# buttons.net
KiCad netlist of a schematic drawn in Altium Designer
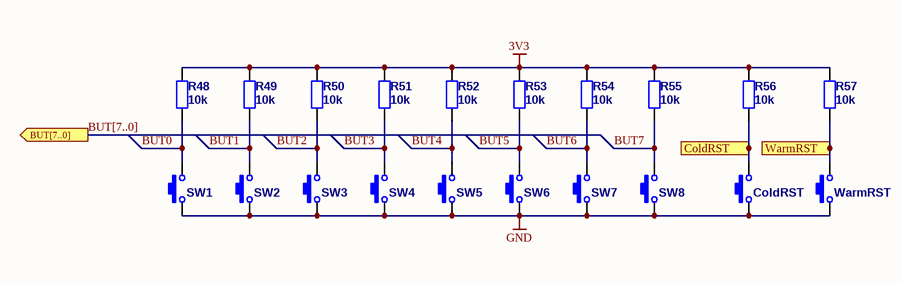
[diagram p0: buttons.SchDoc]

(export (version "E")
  (design (tool "Eeschema 10.0.6"))
  (components
    (comp (ref "ColdRST")
      (value "TACTM-67N-F")
      (footprint "DTSM-6")
      (description "6x6mm SMD Tactile SPST-NO Switch")
      (libsource (lib "microswitches") (part "TACTM-67N-F"))
    )
    (comp (ref "R48")
      (value "10k")
      (footprint "R0603")
      (description "Resistor")
      (libsource (lib "resistors") (part "Res"))
    )
    (comp (ref "R49")
      (value "10k")
      (footprint "R0603")
      (description "Resistor")
      (libsource (lib "resistors") (part "Res"))
    )
    (comp (ref "R50")
      (value "10k")
      (footprint "R0603")
      (description "Resistor")
      (libsource (lib "resistors") (part "Res"))
    )
    (comp (ref "R51")
      (value "10k")
      (footprint "R0603")
      (description "Resistor")
      (libsource (lib "resistors") (part "Res"))
    )
    (comp (ref "R52")
      (value "10k")
      (footprint "R0603")
      (description "Resistor")
      (libsource (lib "resistors") (part "Res"))
    )
    (comp (ref "R53")
      (value "10k")
      (footprint "R0603")
      (description "Resistor")
      (libsource (lib "resistors") (part "Res"))
    )
    (comp (ref "R54")
      (value "10k")
      (footprint "R0603")
      (description "Resistor")
      (libsource (lib "resistors") (part "Res"))
    )
    (comp (ref "R55")
      (value "10k")
      (footprint "R0603")
      (description "Resistor")
      (libsource (lib "resistors") (part "Res"))
    )
    (comp (ref "R56")
      (value "10k")
      (footprint "R0603")
      (description "Resistor")
      (libsource (lib "resistors") (part "Res"))
    )
    (comp (ref "R57")
      (value "10k")
      (footprint "R0603")
      (description "Resistor")
      (libsource (lib "resistors") (part "Res"))
    )
    (comp (ref "SW1")
      (value "TACTM-67N-F")
      (footprint "DTSM-6")
      (description "6x6mm SMD Tactile SPST-NO Switch")
      (libsource (lib "microswitches") (part "TACTM-67N-F"))
    )
    (comp (ref "SW2")
      (value "TACTM-67N-F")
      (footprint "DTSM-6")
      (description "6x6mm SMD Tactile SPST-NO Switch")
      (libsource (lib "microswitches") (part "TACTM-67N-F"))
    )
    (comp (ref "SW3")
      (value "TACTM-67N-F")
      (footprint "DTSM-6")
      (description "6x6mm SMD Tactile SPST-NO Switch")
      (libsource (lib "microswitches") (part "TACTM-67N-F"))
    )
    (comp (ref "SW4")
      (value "TACTM-67N-F")
      (footprint "DTSM-6")
      (description "6x6mm SMD Tactile SPST-NO Switch")
      (libsource (lib "microswitches") (part "TACTM-67N-F"))
    )
    (comp (ref "SW5")
      (value "TACTM-67N-F")
      (footprint "DTSM-6")
      (description "6x6mm SMD Tactile SPST-NO Switch")
      (libsource (lib "microswitches") (part "TACTM-67N-F"))
    )
    (comp (ref "SW6")
      (value "TACTM-67N-F")
      (footprint "DTSM-6")
      (description "6x6mm SMD Tactile SPST-NO Switch")
      (libsource (lib "microswitches") (part "TACTM-67N-F"))
    )
    (comp (ref "SW7")
      (value "TACTM-67N-F")
      (footprint "DTSM-6")
      (description "6x6mm SMD Tactile SPST-NO Switch")
      (libsource (lib "microswitches") (part "TACTM-67N-F"))
    )
    (comp (ref "SW8")
      (value "TACTM-67N-F")
      (footprint "DTSM-6")
      (description "6x6mm SMD Tactile SPST-NO Switch")
      (libsource (lib "microswitches") (part "TACTM-67N-F"))
    )
    (comp (ref "WarmRST")
      (value "TACTM-67N-F")
      (footprint "DTSM-6")
      (description "6x6mm SMD Tactile SPST-NO Switch")
      (libsource (lib "microswitches") (part "TACTM-67N-F"))
    )
  )
  (nets
    (net (code "1") (name "/BUT0") (class "Default")
      (node (ref "R48") (pin "1") (pinfunction "1_1") (pintype "passive"))
      (node (ref "SW1") (pin "2") (pinfunction "2_2") (pintype "passive"))
    )
    (net (code "2") (name "/BUT1") (class "Default")
      (node (ref "R49") (pin "1") (pinfunction "1_1") (pintype "passive"))
      (node (ref "SW2") (pin "2") (pinfunction "2_2") (pintype "passive"))
    )
    (net (code "3") (name "/BUT2") (class "Default")
      (node (ref "R50") (pin "1") (pinfunction "1_1") (pintype "passive"))
      (node (ref "SW3") (pin "2") (pinfunction "2_2") (pintype "passive"))
    )
    (net (code "4") (name "/BUT3") (class "Default")
      (node (ref "R51") (pin "1") (pinfunction "1_1") (pintype "passive"))
      (node (ref "SW4") (pin "2") (pinfunction "2_2") (pintype "passive"))
    )
    (net (code "5") (name "/BUT4") (class "Default")
      (node (ref "R52") (pin "1") (pinfunction "1_1") (pintype "passive"))
      (node (ref "SW5") (pin "2") (pinfunction "2_2") (pintype "passive"))
    )
    (net (code "6") (name "/BUT5") (class "Default")
      (node (ref "R53") (pin "1") (pinfunction "1_1") (pintype "passive"))
      (node (ref "SW6") (pin "2") (pinfunction "2_2") (pintype "passive"))
    )
    (net (code "7") (name "/BUT6") (class "Default")
      (node (ref "R54") (pin "1") (pinfunction "1_1") (pintype "passive"))
      (node (ref "SW7") (pin "2") (pinfunction "2_2") (pintype "passive"))
    )
    (net (code "8") (name "/BUT7") (class "Default")
      (node (ref "R55") (pin "1") (pinfunction "1_1") (pintype "passive"))
      (node (ref "SW8") (pin "2") (pinfunction "2_2") (pintype "passive"))
    )
    (net (code "10") (name "/ColdRST") (class "Default")
      (node (ref "ColdRST") (pin "2") (pinfunction "2_2") (pintype "passive"))
      (node (ref "R56") (pin "1") (pinfunction "1_1") (pintype "passive"))
    )
    (net (code "11") (name "/WarmRST") (class "Default")
      (node (ref "R57") (pin "1") (pinfunction "1_1") (pintype "passive"))
      (node (ref "WarmRST") (pin "2") (pinfunction "2_2") (pintype "passive"))
    )
    (net (code "12") (name "3V3") (class "Default")
      (node (ref "R48") (pin "2") (pinfunction "2_2") (pintype "passive"))
      (node (ref "R49") (pin "2") (pinfunction "2_2") (pintype "passive"))
      (node (ref "R50") (pin "2") (pinfunction "2_2") (pintype "passive"))
      (node (ref "R51") (pin "2") (pinfunction "2_2") (pintype "passive"))
      (node (ref "R52") (pin "2") (pinfunction "2_2") (pintype "passive"))
      (node (ref "R53") (pin "2") (pinfunction "2_2") (pintype "passive"))
      (node (ref "R54") (pin "2") (pinfunction "2_2") (pintype "passive"))
      (node (ref "R55") (pin "2") (pinfunction "2_2") (pintype "passive"))
      (node (ref "R56") (pin "2") (pinfunction "2_2") (pintype "passive"))
      (node (ref "R57") (pin "2") (pinfunction "2_2") (pintype "passive"))
    )
    (net (code "13") (name "GND") (class "Default")
      (node (ref "ColdRST") (pin "1") (pinfunction "1_1") (pintype "passive"))
      (node (ref "SW1") (pin "1") (pinfunction "1_1") (pintype "passive"))
      (node (ref "SW2") (pin "1") (pinfunction "1_1") (pintype "passive"))
      (node (ref "SW3") (pin "1") (pinfunction "1_1") (pintype "passive"))
      (node (ref "SW4") (pin "1") (pinfunction "1_1") (pintype "passive"))
      (node (ref "SW5") (pin "1") (pinfunction "1_1") (pintype "passive"))
      (node (ref "SW6") (pin "1") (pinfunction "1_1") (pintype "passive"))
      (node (ref "SW7") (pin "1") (pinfunction "1_1") (pintype "passive"))
      (node (ref "SW8") (pin "1") (pinfunction "1_1") (pintype "passive"))
      (node (ref "WarmRST") (pin "1") (pinfunction "1_1") (pintype "passive"))
    )
  )
)
